# 20191202_GantryGripper_EA.net
KiCad netlist of a schematic drawn in EAGLE
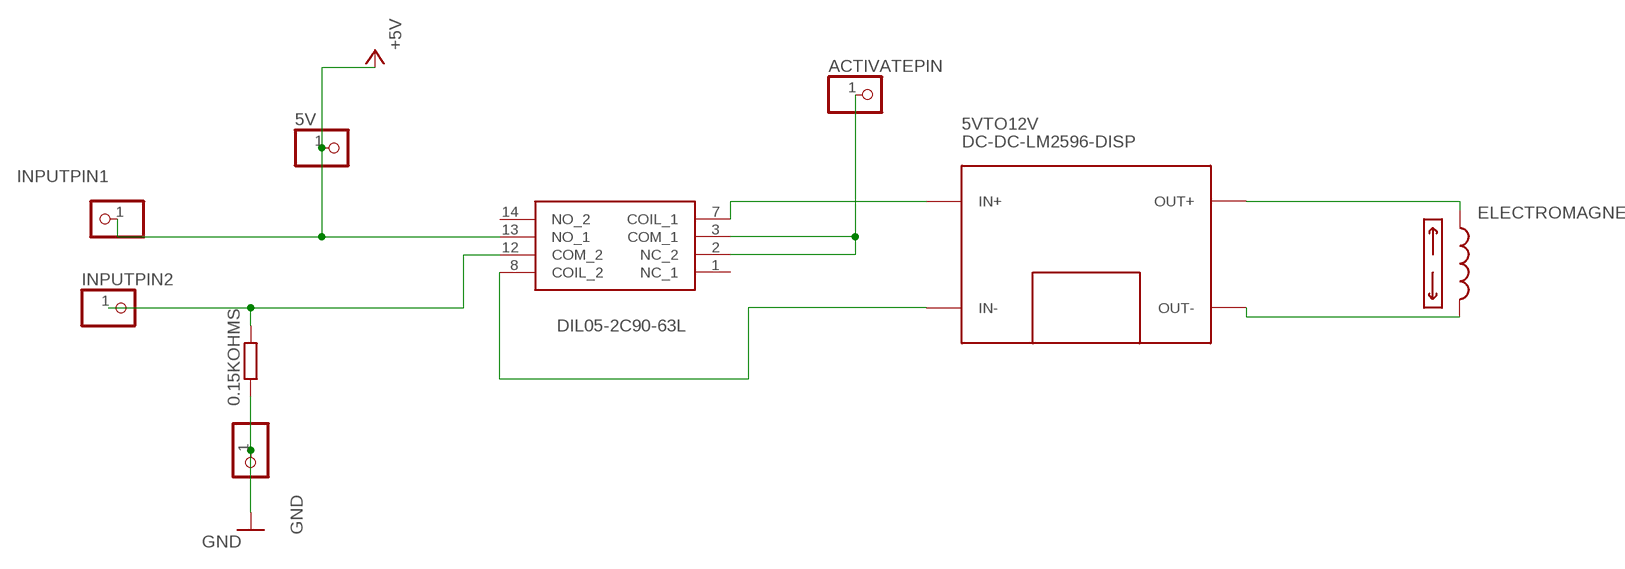
[diagram p0: schematic, sheet 1]

(export (version "E")
  (design (tool "Eeschema 10.0.6"))
  (components
    (comp (ref "0.15KOHMS")
      (value "R-EU_0204/2V")
      (footprint "eagle-import:0204V")
      (libsource (lib "eagle-import") (part "R-EU_0204/2V"))
    )
    (comp (ref "5V")
      (value "PINHD-1X1")
      (footprint "eagle-import:1X01")
      (libsource (lib "eagle-import") (part "PINHD-1X1"))
    )
    (comp (ref "5VTO12V")
      (value "DC-DC-LM2596-DISP")
      (footprint "eagle-import:DC-DC-LM2596-DISP")
      (libsource (lib "eagle-import") (part "DC-DC-LM2596-DISP"))
    )
    (comp (ref "ACTIVATEPIN")
      (value "PINHD-1X1")
      (footprint "eagle-import:1X01")
      (libsource (lib "eagle-import") (part "PINHD-1X1"))
    )
    (comp (ref "ELECTROMAGNET")
      (value "SOLENOID")
      (footprint "eagle-import:1X02")
      (libsource (lib "eagle-import") (part "SOLENOID"))
    )
    (comp (ref "GND")
      (value "PINHD-1X1")
      (footprint "eagle-import:1X01")
      (libsource (lib "eagle-import") (part "PINHD-1X1"))
    )
    (comp (ref "INPUTPIN1")
      (value "PINHD-1X1")
      (footprint "eagle-import:1X01")
      (libsource (lib "eagle-import") (part "PINHD-1X1"))
    )
    (comp (ref "INPUTPIN2")
      (value "PINHD-1X1")
      (footprint "eagle-import:1X01")
      (libsource (lib "eagle-import") (part "PINHD-1X1"))
    )
    (comp (ref "K1")
      (value "DIL05-2C90-63L")
      (footprint "eagle-import:DIL052C9063L")
      (fields (field (name "MOUSER_PART_NUMBER") "876-DIL05-2C90-63L"))
      (libsource (lib "eagle-import") (part "DIL05-2C90-63L"))
    )
  )
  (nets
    (net (code "1") (name "+5V") (class "Default")
      (node (ref "5V") (pin "1") (pinfunction "1_1") (pintype "passive"))
      (node (ref "INPUTPIN1") (pin "1") (pinfunction "1_1") (pintype "passive"))
      (node (ref "K1") (pin "13") (pinfunction "NO_1_13") (pintype "bidirectional"))
    )
    (net (code "2") (name "GND") (class "Default")
      (node (ref "0.15KOHMS") (pin "1") (pinfunction "1_1") (pintype "passive"))
      (node (ref "GND") (pin "1") (pinfunction "1_1") (pintype "passive"))
    )
    (net (code "3") (name "Net-(5VTO12V-PadOUT+)") (class "Default")
      (node (ref "5VTO12V") (pin "OUT+") (pinfunction "OUT+_OUT+") (pintype "bidirectional"))
      (node (ref "ELECTROMAGNET") (pin "1") (pinfunction "1_1") (pintype "passive"))
    )
    (net (code "4") (name "Net-(5VTO12V-PadOUT-)") (class "Default")
      (node (ref "5VTO12V") (pin "OUT-") (pinfunction "OUT-_OUT-") (pintype "bidirectional"))
      (node (ref "ELECTROMAGNET") (pin "2") (pinfunction "2_2") (pintype "passive"))
    )
    (net (code "5") (name "Net-(K1-COIL_1)") (class "Default")
      (node (ref "5VTO12V") (pin "IN+") (pinfunction "IN+_IN+") (pintype "bidirectional"))
      (node (ref "K1") (pin "7") (pinfunction "COIL_1_7") (pintype "bidirectional"))
    )
    (net (code "6") (name "Net-(K1-COIL_2)") (class "Default")
      (node (ref "5VTO12V") (pin "IN-") (pinfunction "IN-_IN-") (pintype "bidirectional"))
      (node (ref "K1") (pin "8") (pinfunction "COIL_2_8") (pintype "bidirectional"))
    )
    (net (code "7") (name "Net-(K1-COM_1)") (class "Default")
      (node (ref "ACTIVATEPIN") (pin "1") (pinfunction "1_1") (pintype "passive"))
      (node (ref "K1") (pin "2") (pinfunction "NC_2_2") (pintype "bidirectional"))
      (node (ref "K1") (pin "3") (pinfunction "COM_1_3") (pintype "bidirectional"))
    )
    (net (code "8") (name "Net-(K1-COM_2)") (class "Default")
      (node (ref "0.15KOHMS") (pin "2") (pinfunction "2_2") (pintype "passive"))
      (node (ref "INPUTPIN2") (pin "1") (pinfunction "1_1") (pintype "passive"))
      (node (ref "K1") (pin "12") (pinfunction "COM_2_12") (pintype "bidirectional"))
    )
    (net (code "9") (name "unconnected-(K1-NC_1-Pad1)") (class "Default")
      (node (ref "K1") (pin "1") (pinfunction "NC_1_1") (pintype "bidirectional"))
    )
    (net (code "10") (name "unconnected-(K1-NO_2-Pad14)") (class "Default")
      (node (ref "K1") (pin "14") (pinfunction "NO_2_14") (pintype "bidirectional"))
    )
  )
)
